# Page-9.net
KiCad netlist of a schematic drawn in Altium Designer
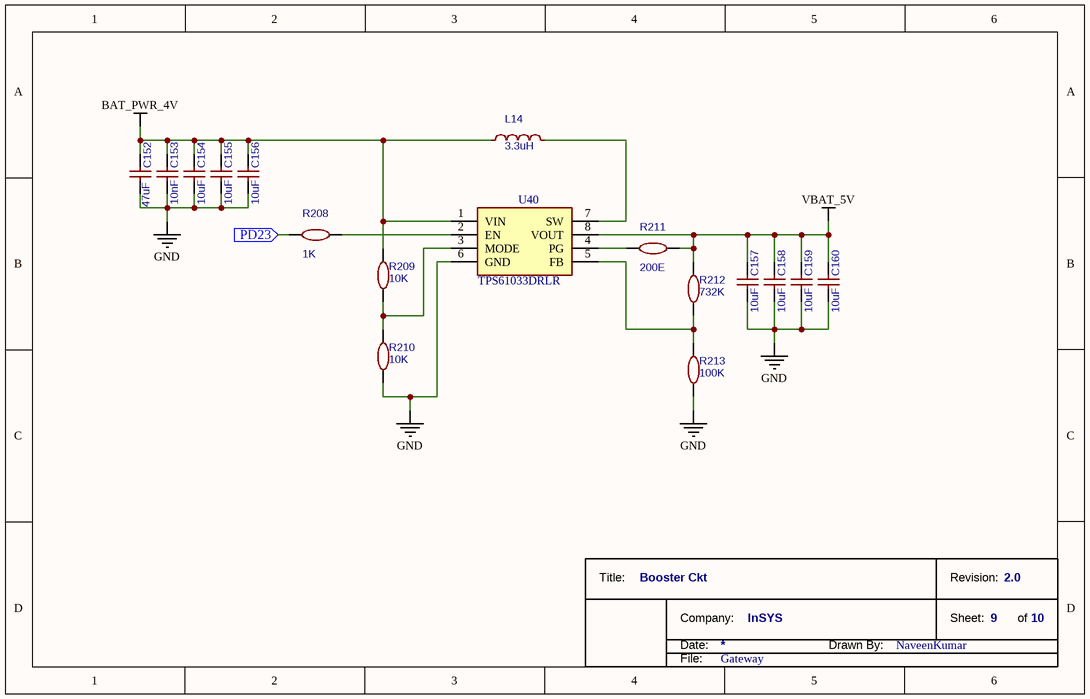
[diagram p0: Page-9.SchDoc]

(export (version "E")
  (design (tool "Eeschema 10.0.6"))
  (components
    (comp (ref "*")
      (value "TitleBlock_1")
      (description "TitleBlock  No-2")
      (fields (field (name "DRAWN BY") "*"))
      (libsource (lib "GateWay_AllwinnerV2") (part "TitleBlock_1"))
    )
    (comp (ref "C152")
      (value "47uF")
      (footprint "GWAY_Capacitor_0603")
      (fields
        (field (name "MANUFACTURER PART") "CL10B105KA8NNNC")
        (field (name "MANUFACTURER") "SAMSUNG(三星)")
      )
      (libsource (lib "altium-import") (part "root_3_1uF_"))
    )
    (comp (ref "C153")
      (value "10nF")
      (footprint "GWAY_Capacitor_0603")
      (fields
        (field (name "MANUFACTURER PART") "CL10B105KA8NNNC")
        (field (name "MANUFACTURER") "SAMSUNG(三星)")
      )
      (libsource (lib "altium-import") (part "root_3_1uF_"))
    )
    (comp (ref "C154")
      (value "10uF")
      (footprint "GWAY_Capacitor_0603")
      (fields
        (field (name "MANUFACTURER PART") "CL10B105KA8NNNC")
        (field (name "MANUFACTURER") "SAMSUNG(三星)")
      )
      (libsource (lib "altium-import") (part "root_3_1uF_"))
    )
    (comp (ref "C155")
      (value "10uF")
      (footprint "GWAY_Capacitor_0603")
      (fields
        (field (name "MANUFACTURER PART") "CL10B105KA8NNNC")
        (field (name "MANUFACTURER") "SAMSUNG(三星)")
      )
      (libsource (lib "altium-import") (part "root_3_1uF_"))
    )
    (comp (ref "C156")
      (value "10uF")
      (footprint "GWAY_Capacitor_0603")
      (fields
        (field (name "MANUFACTURER PART") "CL10B105KA8NNNC")
        (field (name "MANUFACTURER") "SAMSUNG(三星)")
      )
      (libsource (lib "altium-import") (part "root_3_1uF_"))
    )
    (comp (ref "C157")
      (value "10uF")
      (footprint "GWAY_Capacitor_0603")
      (fields
        (field (name "MANUFACTURER PART") "CL10B105KA8NNNC")
        (field (name "MANUFACTURER") "SAMSUNG(三星)")
      )
      (libsource (lib "altium-import") (part "root_3_1uF_"))
    )
    (comp (ref "C158")
      (value "10uF")
      (footprint "GWAY_Capacitor_0603")
      (fields
        (field (name "MANUFACTURER PART") "CL10B105KA8NNNC")
        (field (name "MANUFACTURER") "SAMSUNG(三星)")
      )
      (libsource (lib "altium-import") (part "root_3_1uF_"))
    )
    (comp (ref "C159")
      (value "10uF")
      (footprint "GWAY_Capacitor_0603")
      (fields
        (field (name "MANUFACTURER PART") "CL10B105KA8NNNC")
        (field (name "MANUFACTURER") "SAMSUNG(三星)")
      )
      (libsource (lib "altium-import") (part "root_3_1uF_"))
    )
    (comp (ref "C160")
      (value "10uF")
      (footprint "GWAY_Capacitor_0603")
      (fields
        (field (name "MANUFACTURER PART") "CL10B105KA8NNNC")
        (field (name "MANUFACTURER") "SAMSUNG(三星)")
      )
      (libsource (lib "altium-import") (part "root_3_1uF_"))
    )
    (comp (ref "L14")
      (value "3.3uH")
      (footprint "GWAY_ETQ-P3M_KVP")
      (fields
        (field (name "MANUFACTURER") "TDK")
        (field (name "MANUFACTURER PART") "VLS5045EX-2R2N")
        (field (name "CONTRIBUTOR") "LCSC")
      )
      (libsource (lib "altium-import") (part "root_0_2.2uH_"))
    )
    (comp (ref "R208")
      (value "1K")
      (footprint "GWAY_Resistor_0603")
      (fields (field (name "MANUFACTURER") "YAGEO") (field (name "MANUFACTURER PART") "RC0603JR-0710KL"))
      (libsource (lib "altium-import") (part "root_2_10K_"))
    )
    (comp (ref "R209")
      (value "10K")
      (footprint "GWAY_Resistor_0603")
      (fields (field (name "MANUFACTURER") "YAGEO") (field (name "MANUFACTURER PART") "RC0603JR-0710KL"))
      (libsource (lib "altium-import") (part "root_3_10K_"))
    )
    (comp (ref "R210")
      (value "10K")
      (footprint "GWAY_Resistor_0603")
      (fields (field (name "MANUFACTURER") "YAGEO") (field (name "MANUFACTURER PART") "RC0603JR-0710KL"))
      (libsource (lib "altium-import") (part "root_3_10K_"))
    )
    (comp (ref "R211")
      (value "200E")
      (footprint "GWAY_Resistor_0603")
      (fields (field (name "MANUFACTURER") "YAGEO") (field (name "MANUFACTURER PART") "RC0603JR-0710KL"))
      (libsource (lib "altium-import") (part "root_2_10K_"))
    )
    (comp (ref "R212")
      (value "732K")
      (footprint "GWAY_Resistor_0603")
      (fields (field (name "MANUFACTURER") "YAGEO") (field (name "MANUFACTURER PART") "RC0603JR-0710KL"))
      (libsource (lib "altium-import") (part "root_3_10K_"))
    )
    (comp (ref "R213")
      (value "100K")
      (footprint "GWAY_Resistor_0603")
      (fields (field (name "MANUFACTURER") "YAGEO") (field (name "MANUFACTURER PART") "RC0603JR-0710KL"))
      (libsource (lib "altium-import") (part "root_3_10K_"))
    )
    (comp (ref "U40")
      (value "TPS61033DRLR")
      (description "Power Supply")
      (fields (field (name "MOUSER PART NUMBER") "595-TPS61033DRLR"))
      (libsource (lib "Gateway-RENESAS-Model3") (part "TPS61033DRLR"))
    )
  )
  (nets
    (net (code "1") (name "/PD23") (class "Default")
      (node (ref "R208") (pin "2") (pinfunction "2_2") (pintype "passive"))
    )
    (net (code "2") (name "BAT_PWR_4V") (class "Default")
      (node (ref "C152") (pin "1") (pinfunction "1_1") (pintype "passive"))
      (node (ref "C153") (pin "1") (pinfunction "1_1") (pintype "passive"))
      (node (ref "C154") (pin "1") (pinfunction "1_1") (pintype "passive"))
      (node (ref "C155") (pin "1") (pinfunction "1_1") (pintype "passive"))
      (node (ref "C156") (pin "1") (pinfunction "1_1") (pintype "passive"))
      (node (ref "L14") (pin "1") (pinfunction "1_1") (pintype "passive"))
      (node (ref "R209") (pin "1") (pinfunction "1_1") (pintype "passive"))
      (node (ref "U40") (pin "1") (pinfunction "VIN_1") (pintype "passive"))
    )
    (net (code "3") (name "GND") (class "Default")
      (node (ref "C152") (pin "2") (pinfunction "2_2") (pintype "passive"))
      (node (ref "C153") (pin "2") (pinfunction "2_2") (pintype "passive"))
      (node (ref "C154") (pin "2") (pinfunction "2_2") (pintype "passive"))
      (node (ref "C155") (pin "2") (pinfunction "2_2") (pintype "passive"))
      (node (ref "C156") (pin "2") (pinfunction "2_2") (pintype "passive"))
      (node (ref "C157") (pin "2") (pinfunction "2_2") (pintype "passive"))
      (node (ref "C158") (pin "2") (pinfunction "2_2") (pintype "passive"))
      (node (ref "C159") (pin "2") (pinfunction "2_2") (pintype "passive"))
      (node (ref "C160") (pin "2") (pinfunction "2_2") (pintype "passive"))
      (node (ref "R210") (pin "2") (pinfunction "2_2") (pintype "passive"))
      (node (ref "R213") (pin "2") (pinfunction "2_2") (pintype "passive"))
      (node (ref "U40") (pin "6") (pinfunction "GND_6") (pintype "passive"))
    )
    (net (code "4") (name "Net-(U40-EN)") (class "Default")
      (node (ref "R208") (pin "1") (pinfunction "1_1") (pintype "passive"))
      (node (ref "U40") (pin "2") (pinfunction "EN_2") (pintype "passive"))
    )
    (net (code "5") (name "Net-(U40-FB)") (class "Default")
      (node (ref "R212") (pin "2") (pinfunction "2_2") (pintype "passive"))
      (node (ref "R213") (pin "1") (pinfunction "1_1") (pintype "passive"))
      (node (ref "U40") (pin "5") (pinfunction "FB_5") (pintype "passive"))
    )
    (net (code "6") (name "Net-(U40-MODE)") (class "Default")
      (node (ref "R209") (pin "2") (pinfunction "2_2") (pintype "passive"))
      (node (ref "R210") (pin "1") (pinfunction "1_1") (pintype "passive"))
      (node (ref "U40") (pin "3") (pinfunction "MODE_3") (pintype "passive"))
    )
    (net (code "7") (name "Net-(U40-PG)") (class "Default")
      (node (ref "R211") (pin "2") (pinfunction "2_2") (pintype "passive"))
      (node (ref "U40") (pin "4") (pinfunction "PG_4") (pintype "passive"))
    )
    (net (code "8") (name "Net-(U40-SW)") (class "Default")
      (node (ref "L14") (pin "2") (pinfunction "2_2") (pintype "passive"))
      (node (ref "U40") (pin "7") (pinfunction "SW_7") (pintype "passive"))
    )
    (net (code "9") (name "VBAT_5V") (class "Default")
      (node (ref "C157") (pin "1") (pinfunction "1_1") (pintype "passive"))
      (node (ref "C158") (pin "1") (pinfunction "1_1") (pintype "passive"))
      (node (ref "C159") (pin "1") (pinfunction "1_1") (pintype "passive"))
      (node (ref "C160") (pin "1") (pinfunction "1_1") (pintype "passive"))
      (node (ref "R211") (pin "1") (pinfunction "1_1") (pintype "passive"))
      (node (ref "R212") (pin "1") (pinfunction "1_1") (pintype "passive"))
      (node (ref "U40") (pin "8") (pinfunction "VOUT_8") (pintype "passive"))
    )
  )
)
